# MB_DoorLock293.net
KiCad netlist of a schematic drawn in EAGLE
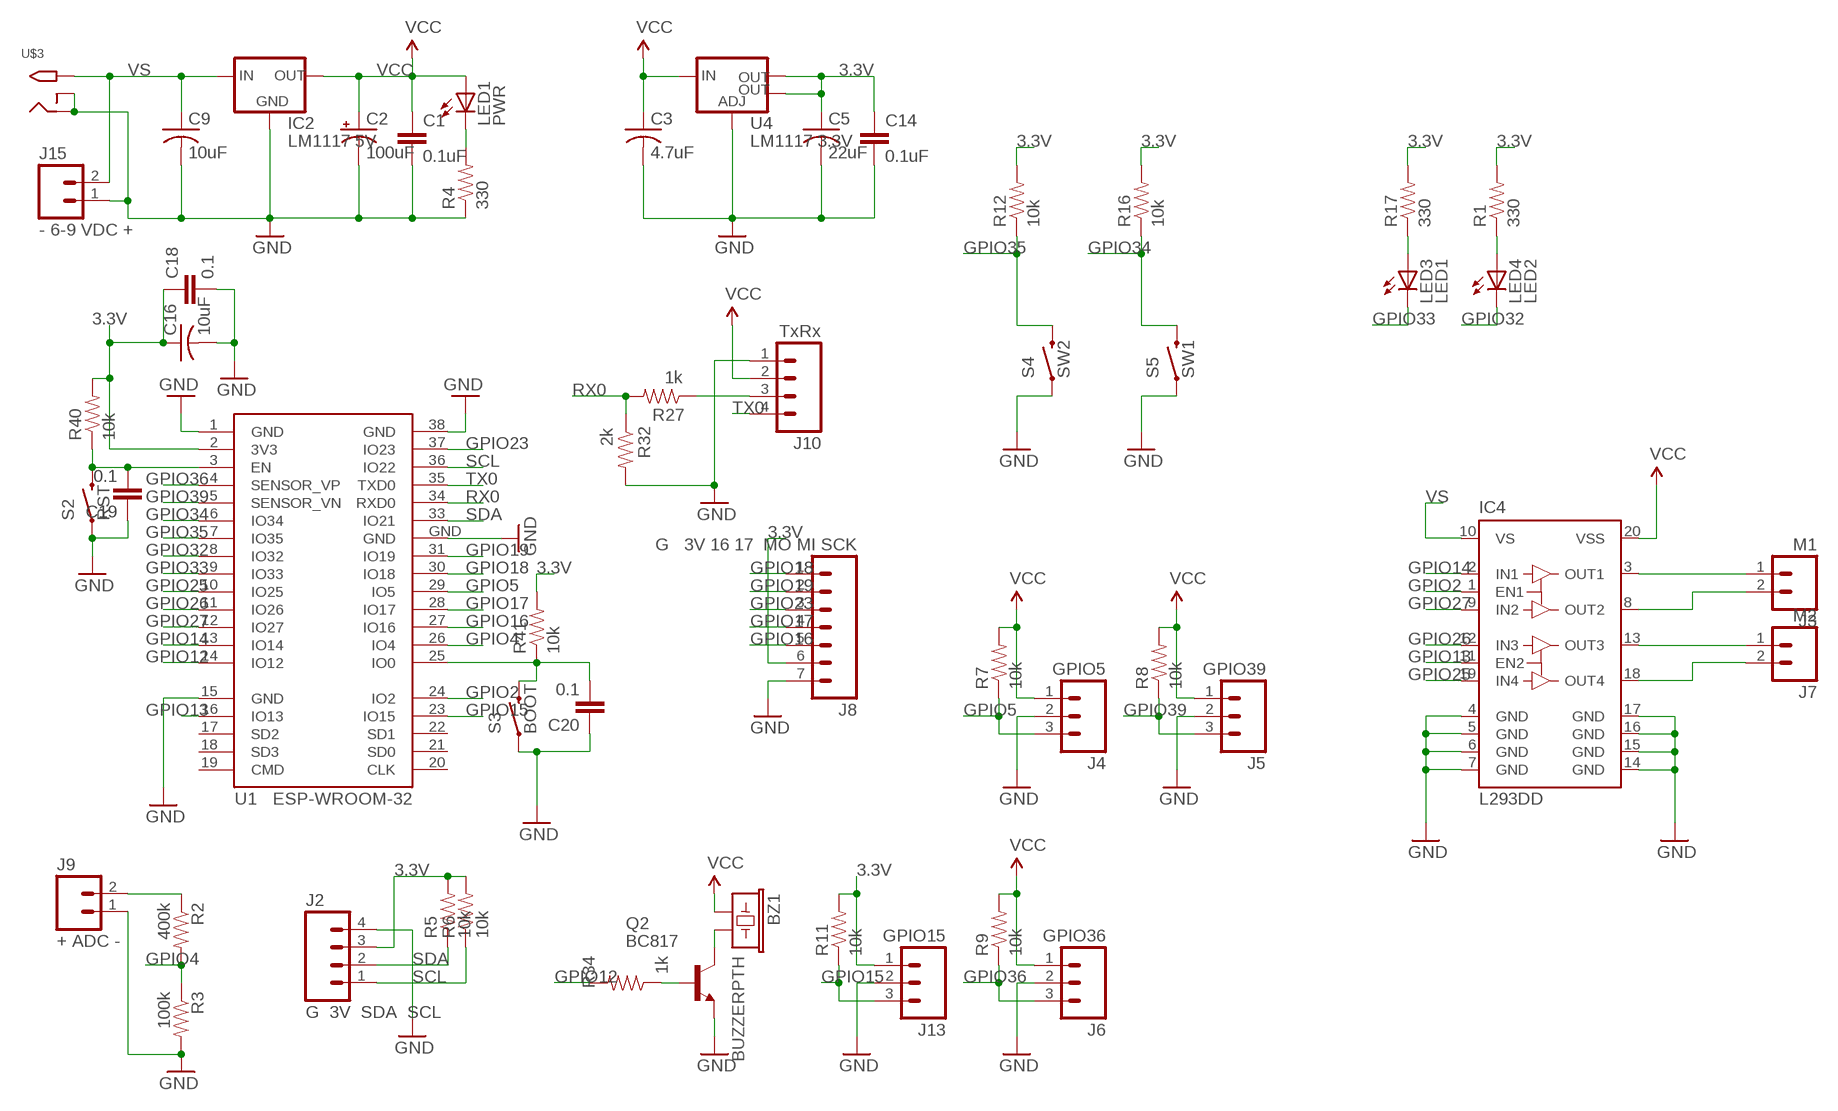
[diagram p0: schematic, sheet 1]

(export (version "E")
  (design (tool "Eeschema 10.0.6"))
  (components
    (comp (ref "BZ1")
      (value "BUZZERPTH")
      (footprint "eagle-import:BUZZER-12MM")
      (libsource (lib "eagle-import") (part "BUZZERPTH"))
    )
    (comp (ref "C1")
      (value "0.1uF")
      (footprint "eagle-import:0805")
      (libsource (lib "eagle-import") (part "CAP0805"))
    )
    (comp (ref "C2")
      (value "100uF")
      (footprint "eagle-import:EIA3528-KIT")
      (libsource (lib "eagle-import") (part "CAP_POL3528-KIT"))
    )
    (comp (ref "C3")
      (value "4.7uF")
      (footprint "eagle-import:C1206")
      (libsource (lib "eagle-import") (part "C-USC1206"))
    )
    (comp (ref "C5")
      (value "22uF")
      (footprint "eagle-import:C1206")
      (libsource (lib "eagle-import") (part "C-USC1206"))
    )
    (comp (ref "C9")
      (value "10uF")
      (footprint "eagle-import:C1206")
      (libsource (lib "eagle-import") (part "C-USC1206"))
    )
    (comp (ref "C14")
      (value "0.1uF")
      (footprint "eagle-import:0805")
      (libsource (lib "eagle-import") (part "CAP0805"))
    )
    (comp (ref "C16")
      (value "10uF")
      (footprint "eagle-import:C1206")
      (libsource (lib "eagle-import") (part "C-USC1206"))
    )
    (comp (ref "C18")
      (value "0.1")
      (footprint "eagle-import:0805")
      (libsource (lib "eagle-import") (part "CAP0805"))
    )
    (comp (ref "C19")
      (value "0.1")
      (footprint "eagle-import:0805")
      (libsource (lib "eagle-import") (part "CAP0805"))
    )
    (comp (ref "C20")
      (value "0.1")
      (footprint "eagle-import:0805")
      (libsource (lib "eagle-import") (part "CAP0805"))
    )
    (comp (ref "IC2")
      (value "LM1117 5V")
      (footprint "eagle-import:TO252")
      (libsource (lib "eagle-import") (part "LM1117DTX-3.3"))
    )
    (comp (ref "IC4")
      (value "L293DD")
      (footprint "eagle-import:SO20")
      (libsource (lib "eagle-import") (part "L293DD"))
    )
    (comp (ref "J2")
      (value "G 3V SDA SCL")
      (footprint "eagle-import:JST-4-PTH-VERT")
      (libsource (lib "eagle-import") (part "M04JST-PTH-VERT"))
    )
    (comp (ref "J3")
      (value "M1")
      (footprint "eagle-import:JST-2-PTH-VERT")
      (libsource (lib "eagle-import") (part "M02JST-PTH-VERT"))
    )
    (comp (ref "J4")
      (value "GPIO5")
      (footprint "eagle-import:JST-3-PTH-VERT")
      (libsource (lib "eagle-import") (part "M03JST-PTH-VERT"))
    )
    (comp (ref "J5")
      (value "GPIO39")
      (footprint "eagle-import:JST-3-PTH-VERT")
      (libsource (lib "eagle-import") (part "M03JST-PTH-VERT"))
    )
    (comp (ref "J6")
      (value "GPIO36")
      (footprint "eagle-import:JST-3-PTH-VERT")
      (libsource (lib "eagle-import") (part "M03JST-PTH-VERT"))
    )
    (comp (ref "J7")
      (value "M2")
      (footprint "eagle-import:JST-2-PTH-VERT")
      (libsource (lib "eagle-import") (part "M02JST-PTH-VERT"))
    )
    (comp (ref "J8")
      (value "G 3V 16 17 MO MI SCK")
      (footprint "eagle-import:1X07")
      (libsource (lib "eagle-import") (part "M07"))
    )
    (comp (ref "J9")
      (value "+ ADC -")
      (footprint "eagle-import:JST-2-PTH-VERT")
      (libsource (lib "eagle-import") (part "M02JST-PTH-VERT"))
    )
    (comp (ref "J10")
      (value "TxRx")
      (footprint "eagle-import:MOLEX-1X4")
      (libsource (lib "eagle-import") (part "M04POLAR"))
    )
    (comp (ref "J13")
      (value "GPIO15")
      (footprint "eagle-import:JST-3-PTH-VERT")
      (libsource (lib "eagle-import") (part "M03JST-PTH-VERT"))
    )
    (comp (ref "J15")
      (value "- 6-9 VDC +")
      (footprint "eagle-import:JST-2-PTH-VERT")
      (libsource (lib "eagle-import") (part "M02JST-PTH-VERT"))
    )
    (comp (ref "LED1")
      (value "PWR")
      (footprint "eagle-import:CHIP-LED0805")
      (libsource (lib "eagle-import") (part "LEDCHIP-LED0805"))
    )
    (comp (ref "LED3")
      (value "LED1")
      (footprint "eagle-import:CHIP-LED0805")
      (libsource (lib "eagle-import") (part "LEDCHIP-LED0805"))
    )
    (comp (ref "LED4")
      (value "LED2")
      (footprint "eagle-import:CHIP-LED0805")
      (libsource (lib "eagle-import") (part "LEDCHIP-LED0805"))
    )
    (comp (ref "Q2")
      (value "BC817")
      (footprint "eagle-import:SOT23-BEC")
      (libsource (lib "eagle-import") (part "BC817SMD-40LT1"))
    )
    (comp (ref "R1")
      (value "330")
      (footprint "eagle-import:0805")
      (libsource (lib "eagle-import") (part "RESISTOR0805-RES"))
    )
    (comp (ref "R2")
      (value "400k")
      (footprint "eagle-import:0805")
      (libsource (lib "eagle-import") (part "RESISTOR0805-RES"))
    )
    (comp (ref "R3")
      (value "100k")
      (footprint "eagle-import:0805")
      (libsource (lib "eagle-import") (part "RESISTOR0805-RES"))
    )
    (comp (ref "R4")
      (value "330")
      (footprint "eagle-import:0805")
      (libsource (lib "eagle-import") (part "RESISTOR0805-RES"))
    )
    (comp (ref "R5")
      (value "10k")
      (footprint "eagle-import:0805")
      (libsource (lib "eagle-import") (part "RESISTOR0805-RES"))
    )
    (comp (ref "R6")
      (value "10k")
      (footprint "eagle-import:0805")
      (libsource (lib "eagle-import") (part "RESISTOR0805-RES"))
    )
    (comp (ref "R7")
      (value "10k")
      (footprint "eagle-import:0805")
      (libsource (lib "eagle-import") (part "RESISTOR0805-RES"))
    )
    (comp (ref "R8")
      (value "10k")
      (footprint "eagle-import:0805")
      (libsource (lib "eagle-import") (part "RESISTOR0805-RES"))
    )
    (comp (ref "R9")
      (value "10k")
      (footprint "eagle-import:0805")
      (libsource (lib "eagle-import") (part "RESISTOR0805-RES"))
    )
    (comp (ref "R11")
      (value "10k")
      (footprint "eagle-import:0805")
      (libsource (lib "eagle-import") (part "RESISTOR0805-RES"))
    )
    (comp (ref "R12")
      (value "10k")
      (footprint "eagle-import:0805")
      (libsource (lib "eagle-import") (part "RESISTOR0805-RES"))
    )
    (comp (ref "R16")
      (value "10k")
      (footprint "eagle-import:0805")
      (libsource (lib "eagle-import") (part "RESISTOR0805-RES"))
    )
    (comp (ref "R17")
      (value "330")
      (footprint "eagle-import:0805")
      (libsource (lib "eagle-import") (part "RESISTOR0805-RES"))
    )
    (comp (ref "R27")
      (value "1k")
      (footprint "eagle-import:0805")
      (libsource (lib "eagle-import") (part "RESISTOR0805-RES"))
    )
    (comp (ref "R32")
      (value "2k")
      (footprint "eagle-import:0805")
      (libsource (lib "eagle-import") (part "RESISTOR0805-RES"))
    )
    (comp (ref "R34")
      (value "1k")
      (footprint "eagle-import:0805")
      (libsource (lib "eagle-import") (part "RESISTOR0805-RES"))
    )
    (comp (ref "R40")
      (value "10k")
      (footprint "eagle-import:0805")
      (libsource (lib "eagle-import") (part "RESISTOR0805-RES"))
    )
    (comp (ref "R41")
      (value "10k")
      (footprint "eagle-import:0805")
      (libsource (lib "eagle-import") (part "RESISTOR0805-RES"))
    )
    (comp (ref "S2")
      (value "RST")
      (footprint "eagle-import:TACTILE-SWITCH-1101NE")
      (libsource (lib "eagle-import") (part "SWITCH-MOMENTARY-2SMD-1101NE"))
    )
    (comp (ref "S3")
      (value "BOOT")
      (footprint "eagle-import:TACTILE-SWITCH-1101NE")
      (libsource (lib "eagle-import") (part "SWITCH-MOMENTARY-2SMD-1101NE"))
    )
    (comp (ref "S4")
      (value "SW2")
      (footprint "eagle-import:TACTILE-SWITCH-1101NE")
      (libsource (lib "eagle-import") (part "SWITCH-MOMENTARY-2SMD-1101NE"))
    )
    (comp (ref "S5")
      (value "SW1")
      (footprint "eagle-import:TACTILE-SWITCH-1101NE")
      (libsource (lib "eagle-import") (part "SWITCH-MOMENTARY-2SMD-1101NE"))
    )
    (comp (ref "U$3")
      (value "7*12V")
      (footprint "eagle-import:PJ-102A")
      (libsource (lib "eagle-import") (part "2.1MMJACK"))
    )
    (comp (ref "U1")
      (value "ESP-WROOM-32")
      (footprint "eagle-import:ESP-WROOM-32")
      (libsource (lib "eagle-import") (part "ESP-WROOM-32"))
    )
    (comp (ref "U4")
      (value "LM1117 3.3V")
      (footprint "eagle-import:SOT223")
      (libsource (lib "eagle-import") (part "V_REG_LM1117SOT223"))
    )
  )
  (nets
    (net (code "1") (name "/3.3V") (class "Default")
      (node (ref "C14") (pin "1") (pinfunction "1_1") (pintype "passive"))
      (node (ref "C16") (pin "1") (pinfunction "1_1") (pintype "passive"))
      (node (ref "C18") (pin "1") (pinfunction "1_1") (pintype "passive"))
      (node (ref "C5") (pin "1") (pinfunction "1_1") (pintype "passive"))
      (node (ref "J13") (pin "1") (pinfunction "1_1") (pintype "passive"))
      (node (ref "J2") (pin "3") (pinfunction "3_3") (pintype "passive"))
      (node (ref "J8") (pin "6") (pinfunction "6_6") (pintype "passive"))
      (node (ref "R1") (pin "2") (pinfunction "2_2") (pintype "passive"))
      (node (ref "R11") (pin "2") (pinfunction "2_2") (pintype "passive"))
      (node (ref "R12") (pin "2") (pinfunction "2_2") (pintype "passive"))
      (node (ref "R16") (pin "2") (pinfunction "2_2") (pintype "passive"))
      (node (ref "R17") (pin "2") (pinfunction "2_2") (pintype "passive"))
      (node (ref "R40") (pin "2") (pinfunction "2_2") (pintype "passive"))
      (node (ref "R41") (pin "2") (pinfunction "2_2") (pintype "passive"))
      (node (ref "R5") (pin "2") (pinfunction "2_2") (pintype "passive"))
      (node (ref "R6") (pin "2") (pinfunction "2_2") (pintype "passive"))
      (node (ref "U1") (pin "2") (pinfunction "3V3_2") (pintype "power_in"))
      (node (ref "U4") (pin "2") (pinfunction "OUT_2") (pintype "output"))
      (node (ref "U4") (pin "4") (pinfunction "OUT_4") (pintype "output"))
    )
    (net (code "2") (name "/GPIO2") (class "Default")
      (node (ref "IC4") (pin "1") (pinfunction "EN1_1") (pintype "input"))
      (node (ref "U1") (pin "24") (pinfunction "IO2_24") (pintype "bidirectional"))
    )
    (net (code "3") (name "/GPIO4") (class "Default")
      (node (ref "R2") (pin "2") (pinfunction "2_2") (pintype "passive"))
      (node (ref "R3") (pin "1") (pinfunction "1_1") (pintype "passive"))
      (node (ref "U1") (pin "26") (pinfunction "IO4_26") (pintype "bidirectional"))
    )
    (net (code "4") (name "/GPIO5") (class "Default")
      (node (ref "J4") (pin "3") (pinfunction "3_3") (pintype "passive"))
      (node (ref "R7") (pin "1") (pinfunction "1_1") (pintype "passive"))
      (node (ref "U1") (pin "29") (pinfunction "IO5_29") (pintype "bidirectional"))
    )
    (net (code "5") (name "/GPIO12") (class "Default")
      (node (ref "R34") (pin "2") (pinfunction "2_2") (pintype "passive"))
      (node (ref "U1") (pin "14") (pinfunction "IO12_14") (pintype "bidirectional"))
    )
    (net (code "6") (name "/GPIO13") (class "Default")
      (node (ref "IC4") (pin "11") (pinfunction "EN2_11") (pintype "input"))
      (node (ref "U1") (pin "16") (pinfunction "IO13_16") (pintype "bidirectional"))
    )
    (net (code "7") (name "/GPIO14") (class "Default")
      (node (ref "IC4") (pin "2") (pinfunction "IN1_2") (pintype "input"))
      (node (ref "U1") (pin "13") (pinfunction "IO14_13") (pintype "bidirectional"))
    )
    (net (code "8") (name "/GPIO15") (class "Default")
      (node (ref "J13") (pin "3") (pinfunction "3_3") (pintype "passive"))
      (node (ref "R11") (pin "1") (pinfunction "1_1") (pintype "passive"))
      (node (ref "U1") (pin "23") (pinfunction "IO15_23") (pintype "bidirectional"))
    )
    (net (code "9") (name "/GPIO16") (class "Default")
      (node (ref "J8") (pin "5") (pinfunction "5_5") (pintype "passive"))
      (node (ref "U1") (pin "27") (pinfunction "IO16_27") (pintype "bidirectional"))
    )
    (net (code "10") (name "/GPIO17") (class "Default")
      (node (ref "J8") (pin "4") (pinfunction "4_4") (pintype "passive"))
      (node (ref "U1") (pin "28") (pinfunction "IO17_28") (pintype "bidirectional"))
    )
    (net (code "11") (name "/GPIO18") (class "Default")
      (node (ref "J8") (pin "1") (pinfunction "1_1") (pintype "passive"))
      (node (ref "U1") (pin "30") (pinfunction "IO18_30") (pintype "bidirectional"))
    )
    (net (code "12") (name "/GPIO19") (class "Default")
      (node (ref "J8") (pin "2") (pinfunction "2_2") (pintype "passive"))
      (node (ref "U1") (pin "31") (pinfunction "IO19_31") (pintype "bidirectional"))
    )
    (net (code "13") (name "/GPIO23") (class "Default")
      (node (ref "J8") (pin "3") (pinfunction "3_3") (pintype "passive"))
      (node (ref "U1") (pin "37") (pinfunction "IO23_37") (pintype "bidirectional"))
    )
    (net (code "14") (name "/GPIO25") (class "Default")
      (node (ref "IC4") (pin "19") (pinfunction "IN4_19") (pintype "input"))
      (node (ref "U1") (pin "10") (pinfunction "IO25_10") (pintype "bidirectional"))
    )
    (net (code "15") (name "/GPIO26") (class "Default")
      (node (ref "IC4") (pin "12") (pinfunction "IN3_12") (pintype "input"))
      (node (ref "U1") (pin "11") (pinfunction "IO26_11") (pintype "bidirectional"))
    )
    (net (code "16") (name "/GPIO27") (class "Default")
      (node (ref "IC4") (pin "9") (pinfunction "IN2_9") (pintype "input"))
      (node (ref "U1") (pin "12") (pinfunction "IO27_12") (pintype "bidirectional"))
    )
    (net (code "17") (name "/GPIO32") (class "Default")
      (node (ref "LED4") (pin "C") (pinfunction "C_C") (pintype "passive"))
      (node (ref "U1") (pin "8") (pinfunction "IO32_8") (pintype "bidirectional"))
    )
    (net (code "18") (name "/GPIO33") (class "Default")
      (node (ref "LED3") (pin "C") (pinfunction "C_C") (pintype "passive"))
      (node (ref "U1") (pin "9") (pinfunction "IO33_9") (pintype "bidirectional"))
    )
    (net (code "19") (name "/GPIO34") (class "Default")
      (node (ref "R16") (pin "1") (pinfunction "1_1") (pintype "passive"))
      (node (ref "S5") (pin "2") (pinfunction "2_2") (pintype "passive"))
      (node (ref "U1") (pin "6") (pinfunction "IO34_6") (pintype "bidirectional"))
    )
    (net (code "20") (name "/GPIO35") (class "Default")
      (node (ref "R12") (pin "1") (pinfunction "1_1") (pintype "passive"))
      (node (ref "S4") (pin "2") (pinfunction "2_2") (pintype "passive"))
      (node (ref "U1") (pin "7") (pinfunction "IO35_7") (pintype "bidirectional"))
    )
    (net (code "21") (name "/GPIO36") (class "Default")
      (node (ref "J6") (pin "3") (pinfunction "3_3") (pintype "passive"))
      (node (ref "R9") (pin "1") (pinfunction "1_1") (pintype "passive"))
      (node (ref "U1") (pin "4") (pinfunction "SENSOR_VP_4") (pintype "bidirectional"))
    )
    (net (code "22") (name "/GPIO39") (class "Default")
      (node (ref "J5") (pin "3") (pinfunction "3_3") (pintype "passive"))
      (node (ref "R8") (pin "1") (pinfunction "1_1") (pintype "passive"))
      (node (ref "U1") (pin "5") (pinfunction "SENSOR_VN_5") (pintype "bidirectional"))
    )
    (net (code "23") (name "/RX0") (class "Default")
      (node (ref "R27") (pin "2") (pinfunction "2_2") (pintype "passive"))
      (node (ref "R32") (pin "1") (pinfunction "1_1") (pintype "passive"))
      (node (ref "U1") (pin "34") (pinfunction "RXD0_34") (pintype "bidirectional"))
    )
    (net (code "24") (name "/SCL") (class "Default")
      (node (ref "J2") (pin "1") (pinfunction "1_1") (pintype "passive"))
      (node (ref "R6") (pin "1") (pinfunction "1_1") (pintype "passive"))
      (node (ref "U1") (pin "36") (pinfunction "IO22_36") (pintype "bidirectional"))
    )
    (net (code "25") (name "/SDA") (class "Default")
      (node (ref "J2") (pin "2") (pinfunction "2_2") (pintype "passive"))
      (node (ref "R5") (pin "1") (pinfunction "1_1") (pintype "passive"))
      (node (ref "U1") (pin "33") (pinfunction "IO21_33") (pintype "bidirectional"))
    )
    (net (code "26") (name "/TX0") (class "Default")
      (node (ref "J10") (pin "4") (pinfunction "4_4") (pintype "passive"))
      (node (ref "U1") (pin "35") (pinfunction "TXD0_35") (pintype "bidirectional"))
    )
    (net (code "27") (name "/VS") (class "Default")
      (node (ref "C9") (pin "1") (pinfunction "1_1") (pintype "passive"))
      (node (ref "IC2") (pin "2") (pinfunction "IN_2") (pintype "input"))
      (node (ref "IC4") (pin "10") (pinfunction "VS_10") (pintype "power_in"))
      (node (ref "J15") (pin "2") (pinfunction "2_2") (pintype "passive"))
      (node (ref "U$3") (pin "TIP") (pinfunction "TIP_TIP") (pintype "bidirectional"))
    )
    (net (code "28") (name "GND") (class "Default")
      (node (ref "C1") (pin "2") (pinfunction "2_2") (pintype "passive"))
      (node (ref "C14") (pin "2") (pinfunction "2_2") (pintype "passive"))
      (node (ref "C16") (pin "2") (pinfunction "2_2") (pintype "passive"))
      (node (ref "C18") (pin "2") (pinfunction "2_2") (pintype "passive"))
      (node (ref "C19") (pin "1") (pinfunction "1_1") (pintype "passive"))
      (node (ref "C2") (pin "C") (pinfunction "-_C") (pintype "passive"))
      (node (ref "C20") (pin "1") (pinfunction "1_1") (pintype "passive"))
      (node (ref "C3") (pin "2") (pinfunction "2_2") (pintype "passive"))
      (node (ref "C5") (pin "2") (pinfunction "2_2") (pintype "passive"))
      (node (ref "C9") (pin "2") (pinfunction "2_2") (pintype "passive"))
      (node (ref "IC2") (pin "1") (pinfunction "GND_1") (pintype "input"))
      (node (ref "IC4") (pin "14") (pinfunction "GND_14") (pintype "power_in"))
      (node (ref "IC4") (pin "15") (pinfunction "GND_15") (pintype "power_in"))
      (node (ref "IC4") (pin "16") (pinfunction "GND_16") (pintype "power_in"))
      (node (ref "IC4") (pin "17") (pinfunction "GND_17") (pintype "power_in"))
      (node (ref "IC4") (pin "4") (pinfunction "GND_4") (pintype "power_in"))
      (node (ref "IC4") (pin "5") (pinfunction "GND_5") (pintype "power_in"))
      (node (ref "IC4") (pin "6") (pinfunction "GND_6") (pintype "power_in"))
      (node (ref "IC4") (pin "7") (pinfunction "GND_7") (pintype "power_in"))
      (node (ref "J10") (pin "1") (pinfunction "1_1") (pintype "passive"))
      (node (ref "J13") (pin "2") (pinfunction "2_2") (pintype "passive"))
      (node (ref "J15") (pin "1") (pinfunction "1_1") (pintype "passive"))
      (node (ref "J2") (pin "4") (pinfunction "4_4") (pintype "passive"))
      (node (ref "J4") (pin "2") (pinfunction "2_2") (pintype "passive"))
      (node (ref "J5") (pin "2") (pinfunction "2_2") (pintype "passive"))
      (node (ref "J6") (pin "2") (pinfunction "2_2") (pintype "passive"))
      (node (ref "J8") (pin "7") (pinfunction "7_7") (pintype "passive"))
      (node (ref "J9") (pin "1") (pinfunction "1_1") (pintype "passive"))
      (node (ref "Q2") (pin "E") (pinfunction "E_E") (pintype "passive"))
      (node (ref "R3") (pin "2") (pinfunction "2_2") (pintype "passive"))
      (node (ref "R32") (pin "2") (pinfunction "2_2") (pintype "passive"))
      (node (ref "R4") (pin "1") (pinfunction "1_1") (pintype "passive"))
      (node (ref "S2") (pin "1") (pinfunction "1_1") (pintype "passive"))
      (node (ref "S3") (pin "1") (pinfunction "1_1") (pintype "passive"))
      (node (ref "S4") (pin "1") (pinfunction "1_1") (pintype "passive"))
      (node (ref "S5") (pin "1") (pinfunction "1_1") (pintype "passive"))
      (node (ref "U$3") (pin "RING") (pinfunction "RING_RING") (pintype "bidirectional"))
      (node (ref "U$3") (pin "RING_SW") (pinfunction "RING_SW_RING_SW") (pintype "bidirectional"))
      (node (ref "U1") (pin "1") (pinfunction "GND_1") (pintype "power_in"))
      (node (ref "U1") (pin "15") (pinfunction "GND_15") (pintype "power_in"))
      (node (ref "U1") (pin "38") (pinfunction "GND_38") (pintype "power_in"))
      (node (ref "U1") (pin "GND") (pinfunction "GND_GND") (pintype "power_in"))
      (node (ref "U4") (pin "1") (pinfunction "ADJ_1") (pintype "input"))
    )
    (net (code "29") (name "Net-(BZ1-2)") (class "Default")
      (node (ref "BZ1") (pin "-") (pinfunction "2_-") (pintype "passive"))
      (node (ref "Q2") (pin "C") (pinfunction "C_C") (pintype "passive"))
    )
    (net (code "30") (name "Net-(IC4-OUT1)") (class "Default")
      (node (ref "IC4") (pin "3") (pinfunction "OUT1_3") (pintype "output"))
      (node (ref "J3") (pin "1") (pinfunction "1_1") (pintype "passive"))
    )
    (net (code "31") (name "Net-(IC4-OUT2)") (class "Default")
      (node (ref "IC4") (pin "8") (pinfunction "OUT2_8") (pintype "output"))
      (node (ref "J3") (pin "2") (pinfunction "2_2") (pintype "passive"))
    )
    (net (code "32") (name "Net-(IC4-OUT3)") (class "Default")
      (node (ref "IC4") (pin "13") (pinfunction "OUT3_13") (pintype "output"))
      (node (ref "J7") (pin "1") (pinfunction "1_1") (pintype "passive"))
    )
    (net (code "33") (name "Net-(IC4-OUT4)") (class "Default")
      (node (ref "IC4") (pin "18") (pinfunction "OUT4_18") (pintype "output"))
      (node (ref "J7") (pin "2") (pinfunction "2_2") (pintype "passive"))
    )
    (net (code "34") (name "Net-(J9-Pad2)") (class "Default")
      (node (ref "J9") (pin "2") (pinfunction "2_2") (pintype "passive"))
      (node (ref "R2") (pin "1") (pinfunction "1_1") (pintype "passive"))
    )
    (net (code "35") (name "Net-(J10-Pad3)") (class "Default")
      (node (ref "J10") (pin "3") (pinfunction "3_3") (pintype "passive"))
      (node (ref "R27") (pin "1") (pinfunction "1_1") (pintype "passive"))
    )
    (net (code "36") (name "Net-(LED1-PadC)") (class "Default")
      (node (ref "LED1") (pin "C") (pinfunction "C_C") (pintype "passive"))
      (node (ref "R4") (pin "2") (pinfunction "2_2") (pintype "passive"))
    )
    (net (code "37") (name "Net-(LED3-PadA)") (class "Default")
      (node (ref "LED3") (pin "A") (pinfunction "A_A") (pintype "passive"))
      (node (ref "R17") (pin "1") (pinfunction "1_1") (pintype "passive"))
    )
    (net (code "38") (name "Net-(LED4-PadA)") (class "Default")
      (node (ref "LED4") (pin "A") (pinfunction "A_A") (pintype "passive"))
      (node (ref "R1") (pin "1") (pinfunction "1_1") (pintype "passive"))
    )
    (net (code "39") (name "Net-(Q2-PadB)") (class "Default")
      (node (ref "Q2") (pin "B") (pinfunction "B_B") (pintype "passive"))
      (node (ref "R34") (pin "1") (pinfunction "1_1") (pintype "passive"))
    )
    (net (code "40") (name "Net-(U1-EN)") (class "Default")
      (node (ref "C19") (pin "2") (pinfunction "2_2") (pintype "passive"))
      (node (ref "R40") (pin "1") (pinfunction "1_1") (pintype "passive"))
      (node (ref "S2") (pin "2") (pinfunction "2_2") (pintype "passive"))
      (node (ref "U1") (pin "3") (pinfunction "EN_3") (pintype "input"))
    )
    (net (code "41") (name "Net-(U1-IO0)") (class "Default")
      (node (ref "C20") (pin "2") (pinfunction "2_2") (pintype "passive"))
      (node (ref "R41") (pin "1") (pinfunction "1_1") (pintype "passive"))
      (node (ref "S3") (pin "2") (pinfunction "2_2") (pintype "passive"))
      (node (ref "U1") (pin "25") (pinfunction "IO0_25") (pintype "bidirectional"))
    )
    (net (code "42") (name "VCC") (class "Default")
      (node (ref "BZ1") (pin "+") (pinfunction "1_+") (pintype "passive"))
      (node (ref "C1") (pin "1") (pinfunction "1_1") (pintype "passive"))
      (node (ref "C2") (pin "A") (pinfunction "+_A") (pintype "passive"))
      (node (ref "C3") (pin "1") (pinfunction "1_1") (pintype "passive"))
      (node (ref "IC2") (pin "TAB") (pinfunction "OUT_TAB") (pintype "passive"))
      (node (ref "IC4") (pin "20") (pinfunction "VSS_20") (pintype "power_in"))
      (node (ref "J10") (pin "2") (pinfunction "2_2") (pintype "passive"))
      (node (ref "J4") (pin "1") (pinfunction "1_1") (pintype "passive"))
      (node (ref "J5") (pin "1") (pinfunction "1_1") (pintype "passive"))
      (node (ref "J6") (pin "1") (pinfunction "1_1") (pintype "passive"))
      (node (ref "LED1") (pin "A") (pinfunction "A_A") (pintype "passive"))
      (node (ref "R7") (pin "2") (pinfunction "2_2") (pintype "passive"))
      (node (ref "R8") (pin "2") (pinfunction "2_2") (pintype "passive"))
      (node (ref "R9") (pin "2") (pinfunction "2_2") (pintype "passive"))
      (node (ref "U4") (pin "3") (pinfunction "IN_3") (pintype "input"))
    )
    (net (code "43") (name "unconnected-(U1-CLK-Pad20)") (class "Default")
      (node (ref "U1") (pin "20") (pinfunction "CLK_20") (pintype "bidirectional"))
    )
    (net (code "44") (name "unconnected-(U1-CMD-Pad19)") (class "Default")
      (node (ref "U1") (pin "19") (pinfunction "CMD_19") (pintype "bidirectional"))
    )
    (net (code "45") (name "unconnected-(U1-SD0-Pad21)") (class "Default")
      (node (ref "U1") (pin "21") (pinfunction "SD0_21") (pintype "bidirectional"))
    )
    (net (code "46") (name "unconnected-(U1-SD1-Pad22)") (class "Default")
      (node (ref "U1") (pin "22") (pinfunction "SD1_22") (pintype "bidirectional"))
    )
    (net (code "47") (name "unconnected-(U1-SD2-Pad17)") (class "Default")
      (node (ref "U1") (pin "17") (pinfunction "SD2_17") (pintype "bidirectional"))
    )
    (net (code "48") (name "unconnected-(U1-SD3-Pad18)") (class "Default")
      (node (ref "U1") (pin "18") (pinfunction "SD3_18") (pintype "bidirectional"))
    )
  )
)
